# connectors.net
KiCad netlist of a schematic drawn in Altium Designer
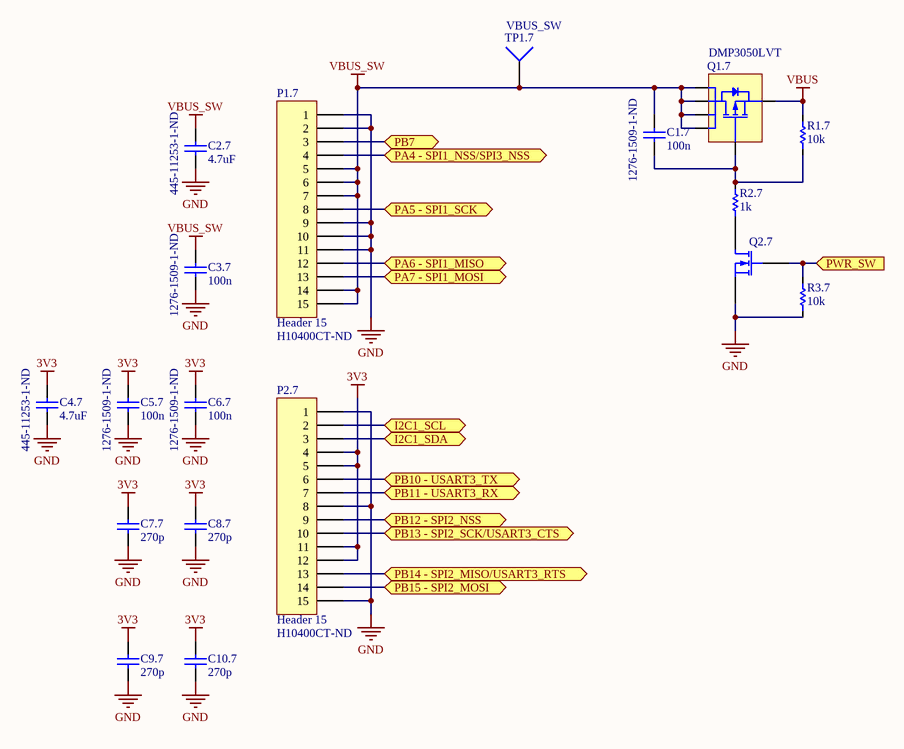
[diagram p0: connectors.SchDoc]

(export (version "E")
  (design (tool "Eeschema 10.0.6"))
  (components
    (comp (ref "C1.7")
      (value "100n")
      (footprint "0402")
      (fields (field (name "SUPPLIER PART NUMBER 1") "1276-1509-1-ND"))
      (libsource (lib "Luminaire") (part "CAPACITOR NON_POL"))
    )
    (comp (ref "C2.7")
      (value "4.7uF")
      (footprint "1608[0603]")
      (fields (field (name "SUPPLIER PART NUMBER 1") "445-11253-1-ND"))
      (libsource (lib "KEMET Chip Capacitor") (part "C0402"))
    )
    (comp (ref "C3.7")
      (value "100n")
      (footprint "0402")
      (fields (field (name "SUPPLIER PART NUMBER 1") "1276-1509-1-ND"))
      (libsource (lib "Luminaire") (part "CAPACITOR NON_POL"))
    )
    (comp (ref "C4.7")
      (value "4.7uF")
      (footprint "1608[0603]")
      (fields (field (name "SUPPLIER PART NUMBER 1") "445-11253-1-ND"))
      (libsource (lib "KEMET Chip Capacitor") (part "C0402"))
    )
    (comp (ref "C5.7")
      (value "100n")
      (footprint "0402")
      (fields (field (name "SUPPLIER PART NUMBER 1") "1276-1509-1-ND"))
      (libsource (lib "Luminaire") (part "CAPACITOR NON_POL"))
    )
    (comp (ref "C6.7")
      (value "100n")
      (footprint "0402")
      (fields (field (name "SUPPLIER PART NUMBER 1") "1276-1509-1-ND"))
      (libsource (lib "Luminaire") (part "CAPACITOR NON_POL"))
    )
    (comp (ref "C7.7") (value "270p") (footprint "0402") (libsource (lib "pokey") (part "CAPACITOR NON_POL")))
    (comp (ref "C8.7") (value "270p") (footprint "0402") (libsource (lib "pokey") (part "CAPACITOR NON_POL")))
    (comp (ref "C9.7") (value "270p") (footprint "0402") (libsource (lib "pokey") (part "CAPACITOR NON_POL")))
    (comp (ref "C10.7")
      (value "270p")
      (footprint "0402")
      (libsource (lib "pokey") (part "CAPACITOR NON_POL"))
    )
    (comp (ref "P1.7")
      (value "Header 15")
      (footprint "DF9-15S-1V")
      (description "Header, 15-Pin")
      (fields
        (field (name "SUPPLIER PART NUMBER 1") "H10400CT-ND")
        (field (name "PUBLISHER") "Altium Limited")
      )
      (libsource (lib "Miscellaneous Connectors") (part "Header 15"))
    )
    (comp (ref "P2.7")
      (value "Header 15")
      (footprint "DF9-15S-1V")
      (description "Header, 15-Pin")
      (fields
        (field (name "SUPPLIER PART NUMBER 1") "H10400CT-ND")
        (field (name "PUBLISHER") "Altium Limited")
      )
      (libsource (lib "Miscellaneous Connectors") (part "Header 15"))
    )
    (comp (ref "Q1.7")
      (value "DMP3050LVT")
      (footprint "SOT95P280X100-6N")
      (libsource (lib "pokey") (part "DMP3050LVT"))
    )
    (comp (ref "Q2.7")
      (value "2N7002")
      (footprint "SOT23")
      (description "N-Channel Enhancement Mode Vertical DMOS FET")
      (libsource (lib "pokey") (part "2N7002"))
    )
    (comp (ref "R1.7")
      (value "10k")
      (footprint "0402")
      (fields
        (field (name "MANUFACTURER") "Yageo")
        (field (name "MANUFACTURER PART NUMBER") "RC0402JR-0710KL")
        (field (name "TOLERANCE") "±5%")
      )
      (libsource (lib "Luminaire") (part "RESISTOR"))
    )
    (comp (ref "R2.7") (value "1k") (footprint "0402") (libsource (lib "pokey") (part "RESISTOR")))
    (comp (ref "R3.7")
      (value "10k")
      (footprint "0402")
      (fields
        (field (name "MANUFACTURER") "Yageo")
        (field (name "MANUFACTURER PART NUMBER") "RC0402JR-0710KL")
        (field (name "TOLERANCE") "±5%")
      )
      (libsource (lib "Luminaire") (part "RESISTOR"))
    )
    (comp (ref "TP1.7")
      (value "VBUS_SW")
      (footprint "Test Point Target 1mm")
      (description "Socket")
      (fields (field (name "PUBLISHER") "Altium Limited"))
      (libsource (lib "Miscellaneous Connectors") (part "Socket"))
    )
  )
  (nets
    (net (code "1") (name "/I2C1_SCL") (class "Default")
      (node (ref "P2.7") (pin "2") (pinfunction "2_2") (pintype "passive"))
    )
    (net (code "2") (name "/I2C1_SDA") (class "Default")
      (node (ref "P2.7") (pin "3") (pinfunction "3_3") (pintype "passive"))
    )
    (net (code "3") (name "/PA4 - SPI1_NSS{slash}SPI3_NSS") (class "Default")
      (node (ref "P1.7") (pin "4") (pinfunction "4_4") (pintype "passive"))
    )
    (net (code "4") (name "/PA5 - SPI1_SCK") (class "Default")
      (node (ref "P1.7") (pin "8") (pinfunction "8_8") (pintype "passive"))
    )
    (net (code "5") (name "/PA6 - SPI1_MISO") (class "Default")
      (node (ref "P1.7") (pin "12") (pinfunction "12_12") (pintype "passive"))
    )
    (net (code "6") (name "/PA7 - SPI1_MOSI") (class "Default")
      (node (ref "P1.7") (pin "13") (pinfunction "13_13") (pintype "passive"))
    )
    (net (code "7") (name "/PB7") (class "Default")
      (node (ref "P1.7") (pin "3") (pinfunction "3_3") (pintype "passive"))
    )
    (net (code "8") (name "/PB10 - USART3_TX") (class "Default")
      (node (ref "P2.7") (pin "6") (pinfunction "6_6") (pintype "passive"))
    )
    (net (code "9") (name "/PB11 - USART3_RX") (class "Default")
      (node (ref "P2.7") (pin "7") (pinfunction "7_7") (pintype "passive"))
    )
    (net (code "10") (name "/PB12 - SPI2_NSS") (class "Default")
      (node (ref "P2.7") (pin "9") (pinfunction "9_9") (pintype "passive"))
    )
    (net (code "11") (name "/PB13 - SPI2_SCK{slash}USART3_CTS") (class "Default")
      (node (ref "P2.7") (pin "10") (pinfunction "10_10") (pintype "passive"))
    )
    (net (code "12") (name "/PB14 - SPI2_MISO{slash}USART3_RTS") (class "Default")
      (node (ref "P2.7") (pin "13") (pinfunction "13_13") (pintype "passive"))
    )
    (net (code "13") (name "/PB15 - SPI2_MOSI") (class "Default")
      (node (ref "P2.7") (pin "14") (pinfunction "14_14") (pintype "passive"))
    )
    (net (code "14") (name "/PWR_SW") (class "Default")
      (node (ref "Q2.7") (pin "3") (pinfunction "G_3") (pintype "passive"))
      (node (ref "R3.7") (pin "2") (pinfunction "2_2") (pintype "passive"))
    )
    (net (code "15") (name "3V3") (class "Default")
      (node (ref "C10.7") (pin "2") (pinfunction "2_2") (pintype "passive"))
      (node (ref "C4.7") (pin "2") (pinfunction "2_2") (pintype "passive"))
      (node (ref "C5.7") (pin "1") (pinfunction "1_1") (pintype "passive"))
      (node (ref "C6.7") (pin "1") (pinfunction "1_1") (pintype "passive"))
      (node (ref "C7.7") (pin "2") (pinfunction "2_2") (pintype "passive"))
      (node (ref "C8.7") (pin "2") (pinfunction "2_2") (pintype "passive"))
      (node (ref "C9.7") (pin "2") (pinfunction "2_2") (pintype "passive"))
      (node (ref "P2.7") (pin "11") (pinfunction "11_11") (pintype "passive"))
      (node (ref "P2.7") (pin "12") (pinfunction "12_12") (pintype "passive"))
      (node (ref "P2.7") (pin "4") (pinfunction "4_4") (pintype "passive"))
      (node (ref "P2.7") (pin "5") (pinfunction "5_5") (pintype "passive"))
    )
    (net (code "16") (name "GND") (class "Default")
      (node (ref "C10.7") (pin "1") (pinfunction "1_1") (pintype "passive"))
      (node (ref "C2.7") (pin "1") (pinfunction "1_1") (pintype "passive"))
      (node (ref "C3.7") (pin "2") (pinfunction "2_2") (pintype "passive"))
      (node (ref "C4.7") (pin "1") (pinfunction "1_1") (pintype "passive"))
      (node (ref "C5.7") (pin "2") (pinfunction "2_2") (pintype "passive"))
      (node (ref "C6.7") (pin "2") (pinfunction "2_2") (pintype "passive"))
      (node (ref "C7.7") (pin "1") (pinfunction "1_1") (pintype "passive"))
      (node (ref "C8.7") (pin "1") (pinfunction "1_1") (pintype "passive"))
      (node (ref "C9.7") (pin "1") (pinfunction "1_1") (pintype "passive"))
      (node (ref "P1.7") (pin "1") (pinfunction "1_1") (pintype "passive"))
      (node (ref "P1.7") (pin "10") (pinfunction "10_10") (pintype "passive"))
      (node (ref "P1.7") (pin "11") (pinfunction "11_11") (pintype "passive"))
      (node (ref "P1.7") (pin "2") (pinfunction "2_2") (pintype "passive"))
      (node (ref "P1.7") (pin "9") (pinfunction "9_9") (pintype "passive"))
      (node (ref "P2.7") (pin "1") (pinfunction "1_1") (pintype "passive"))
      (node (ref "P2.7") (pin "15") (pinfunction "15_15") (pintype "passive"))
      (node (ref "P2.7") (pin "8") (pinfunction "8_8") (pintype "passive"))
      (node (ref "Q2.7") (pin "2") (pinfunction "S_2") (pintype "passive"))
      (node (ref "R3.7") (pin "1") (pinfunction "1_1") (pintype "passive"))
    )
    (net (code "17") (name "Net-(Q1.7-G)") (class "Default")
      (node (ref "C1.7") (pin "2") (pinfunction "2_2") (pintype "passive"))
      (node (ref "Q1.7") (pin "3") (pinfunction "G_3") (pintype "power_in"))
      (node (ref "R1.7") (pin "1") (pinfunction "1_1") (pintype "passive"))
      (node (ref "R2.7") (pin "2") (pinfunction "2_2") (pintype "passive"))
    )
    (net (code "18") (name "Net-(Q2.7-D)") (class "Default")
      (node (ref "Q2.7") (pin "1") (pinfunction "D_1") (pintype "passive"))
      (node (ref "R2.7") (pin "1") (pinfunction "1_1") (pintype "passive"))
    )
    (net (code "19") (name "VBUS") (class "Default")
      (node (ref "Q1.7") (pin "4") (pinfunction "S_4") (pintype "power_in"))
      (node (ref "R1.7") (pin "2") (pinfunction "2_2") (pintype "passive"))
    )
    (net (code "20") (name "VBUS_SW") (class "Default")
      (node (ref "C1.7") (pin "1") (pinfunction "1_1") (pintype "passive"))
      (node (ref "C2.7") (pin "2") (pinfunction "2_2") (pintype "passive"))
      (node (ref "C3.7") (pin "1") (pinfunction "1_1") (pintype "passive"))
      (node (ref "P1.7") (pin "14") (pinfunction "14_14") (pintype "passive"))
      (node (ref "P1.7") (pin "15") (pinfunction "15_15") (pintype "passive"))
      (node (ref "P1.7") (pin "5") (pinfunction "5_5") (pintype "passive"))
      (node (ref "P1.7") (pin "6") (pinfunction "6_6") (pintype "passive"))
      (node (ref "P1.7") (pin "7") (pinfunction "7_7") (pintype "passive"))
      (node (ref "Q1.7") (pin "1") (pinfunction "D_1") (pintype "power_in"))
      (node (ref "Q1.7") (pin "2") (pinfunction "D_2") (pintype "power_in"))
      (node (ref "Q1.7") (pin "5") (pinfunction "D_5") (pintype "power_in"))
      (node (ref "Q1.7") (pin "6") (pinfunction "D_6") (pintype "power_in"))
      (node (ref "TP1.7") (pin "1") (pinfunction "1_1") (pintype "passive"))
    )
  )
)
